# controleo3_clone.net
KiCad netlist of a schematic drawn in Altium Designer
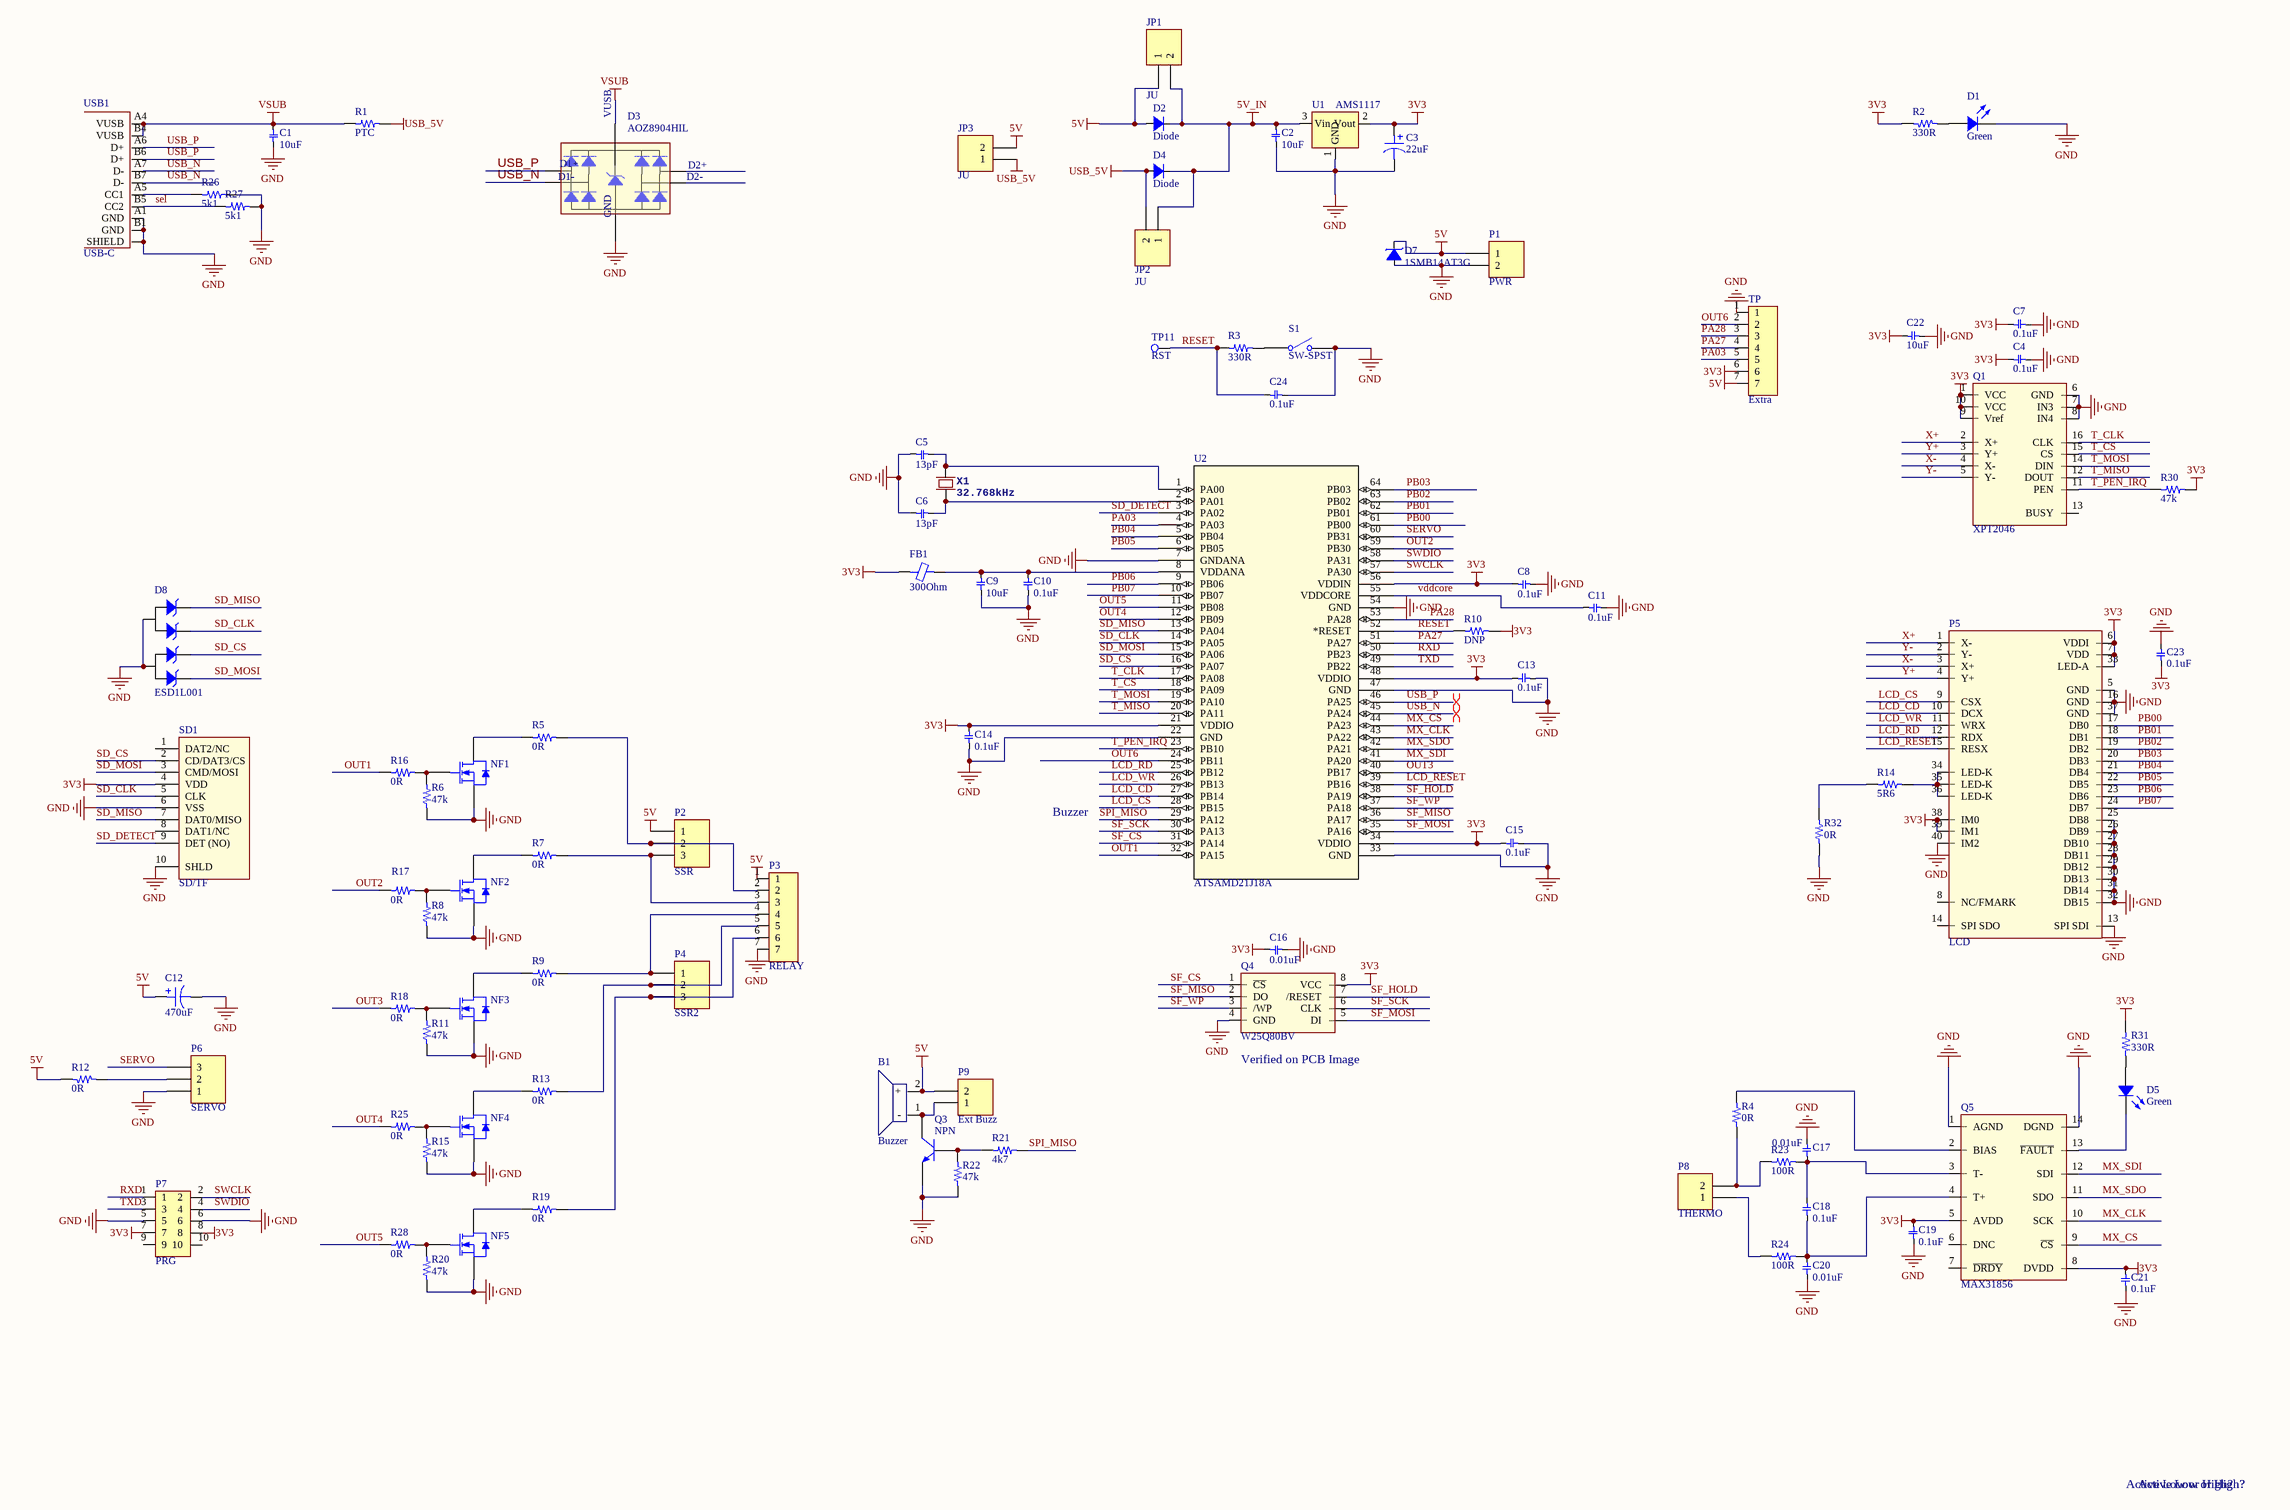
[diagram p0: controleo3_clone.SchDoc]

(export (version "E")
  (design (tool "Eeschema 10.0.6"))
  (components
    (comp (ref "B1") (value "Buzzer") (footprint "Buzzer") (libsource (lib "BMI") (part "Buzzer")))
    (comp (ref "C1")
      (value "10uF")
      (footprint "CAP 0805/2012 RF")
      (description "SMT Capacitor")
      (libsource (lib "Passives") (part "Capacitor Mini Symbol"))
    )
    (comp (ref "C2")
      (value "10uF")
      (footprint "CAP 0805/2012 RF")
      (description "SMT Capacitor")
      (libsource (lib "Passives") (part "Capacitor Mini Symbol"))
    )
    (comp (ref "C3")
      (value "22uF")
      (footprint "CAP Pol 1210/3225 - 2.5MM")
      (libsource (lib "Passives") (part "SMT Tantalum Capacitor"))
    )
    (comp (ref "C4")
      (value "0.1uF")
      (footprint "CAP 0603 RF")
      (description "SMT Capacitor")
      (libsource (lib "Passives") (part "Capacitor Mini Symbol"))
    )
    (comp (ref "C5")
      (value "13pF")
      (footprint "CAP 0603 RF")
      (description "SMT Capacitor")
      (libsource (lib "Passives") (part "Capacitor Mini Symbol"))
    )
    (comp (ref "C6")
      (value "13pF")
      (footprint "CAP 0603 RF")
      (description "SMT Capacitor")
      (libsource (lib "Passives") (part "Capacitor Mini Symbol"))
    )
    (comp (ref "C7")
      (value "0.1uF")
      (footprint "CAP 0603 RF")
      (description "SMT Capacitor")
      (libsource (lib "Passives") (part "Capacitor Mini Symbol"))
    )
    (comp (ref "C8")
      (value "0.1uF")
      (footprint "CAP 0603 RF")
      (description "SMT Capacitor")
      (libsource (lib "Passives") (part "Capacitor Mini Symbol"))
    )
    (comp (ref "C9")
      (value "10uF")
      (footprint "CAP 0603 RF")
      (description "SMT Capacitor")
      (libsource (lib "Passives") (part "Capacitor Mini Symbol"))
    )
    (comp (ref "C10")
      (value "0.1uF")
      (footprint "CAP 0603 RF")
      (description "SMT Capacitor")
      (libsource (lib "Passives") (part "Capacitor Mini Symbol"))
    )
    (comp (ref "C11")
      (value "0.1uF")
      (footprint "CAP 0603 RF")
      (description "SMT Capacitor")
      (libsource (lib "Passives") (part "Capacitor Mini Symbol"))
    )
    (comp (ref "C12")
      (value "470uF")
      (footprint "CAP ALUM 8.0MM Size E")
      (description "SMT Aluminum Capacitor")
      (libsource (lib "Passives") (part "SMT Aluminum Capacitor"))
    )
    (comp (ref "C13")
      (value "0.1uF")
      (footprint "CAP 0603 RF")
      (description "SMT Capacitor")
      (libsource (lib "Passives") (part "Capacitor Mini Symbol"))
    )
    (comp (ref "C14")
      (value "0.1uF")
      (footprint "CAP 0603 RF")
      (description "SMT Capacitor")
      (libsource (lib "Passives") (part "Capacitor Mini Symbol"))
    )
    (comp (ref "C15")
      (value "0.1uF")
      (footprint "CAP 0603 RF")
      (description "SMT Capacitor")
      (libsource (lib "Passives") (part "Capacitor Mini Symbol"))
    )
    (comp (ref "C16")
      (value "0.01uF")
      (footprint "CAP 0603 RF")
      (description "SMT Capacitor")
      (libsource (lib "Passives") (part "Capacitor Mini Symbol"))
    )
    (comp (ref "C17")
      (value "0.01uF")
      (footprint "CAP 0603 RF")
      (description "SMT Capacitor")
      (libsource (lib "Passives") (part "Capacitor Mini Symbol"))
    )
    (comp (ref "C18")
      (value "0.1uF")
      (footprint "CAP 0603 RF")
      (description "SMT Capacitor")
      (libsource (lib "Passives") (part "Capacitor Mini Symbol"))
    )
    (comp (ref "C19")
      (value "0.1uF")
      (footprint "CAP 0603 RF")
      (description "SMT Capacitor")
      (libsource (lib "Passives") (part "Capacitor Mini Symbol"))
    )
    (comp (ref "C20")
      (value "0.01uF")
      (footprint "CAP 0603 RF")
      (description "SMT Capacitor")
      (libsource (lib "Passives") (part "Capacitor Mini Symbol"))
    )
    (comp (ref "C21")
      (value "0.1uF")
      (footprint "CAP 0603 RF")
      (description "SMT Capacitor")
      (libsource (lib "Passives") (part "Capacitor Mini Symbol"))
    )
    (comp (ref "C22")
      (value "10uF")
      (footprint "CAP 0805/2012 RF")
      (description "SMT Capacitor")
      (libsource (lib "Passives") (part "Capacitor Mini Symbol"))
    )
    (comp (ref "C23")
      (value "0.1uF")
      (footprint "CAP 0603 RF")
      (description "SMT Capacitor")
      (libsource (lib "Passives") (part "Capacitor Mini Symbol"))
    )
    (comp (ref "C24")
      (value "0.1uF")
      (footprint "CAP 0603 RF")
      (description "SMT Capacitor")
      (libsource (lib "Passives") (part "Capacitor Mini Symbol"))
    )
    (comp (ref "D1")
      (value "Green")
      (footprint "LED 0603/1608 RF - Red")
      (description "Chip LED")
      (libsource (lib "BMI") (part "LED"))
    )
    (comp (ref "D2") (value "Diode") (footprint "SOD-123F") (libsource (lib "BMI") (part "Diode")))
    (comp (ref "D3")
      (value "AOZ8904HIL")
      (footprint "SOT-23 (6) - Medium")
      (description "ESD Protection Diode")
      (libsource (lib "BMI") (part "ESD Diode USB"))
    )
    (comp (ref "D4") (value "Diode") (footprint "SOD-123F") (libsource (lib "BMI") (part "Diode")))
    (comp (ref "D5")
      (value "Green")
      (footprint "LED 0603/1608 RF - Red")
      (description "Chip LED")
      (libsource (lib "BMI") (part "LED"))
    )
    (comp (ref "D7")
      (value "1SMB14AT3G")
      (footprint "SMB")
      (description "TVS Diode")
      (libsource (lib "BMI") (part "TVS Diode"))
    )
    (comp (ref "D8")
      (value "ESD1L001")
      (footprint "SC-70-6 - NC7WZ16-D")
      (description "ESD Protection Diode Array")
      (libsource (lib "BMI") (part "ESD Diode Array"))
    )
    (comp (ref "FB1")
      (value "300Ohm")
      (footprint "RES 0603/1608 RF")
      (description "SMT Ferrite Chip")
      (libsource (lib "Passives") (part "Ferrite Chip"))
    )
    (comp (ref "JP1")
      (value "JU")
      (footprint "J2")
      (description "Header, 2-Pin, Right Angle")
      (fields (field (name "PUBLISHER") "Altium Limited"))
      (libsource (lib "") (part "Header 2H_1"))
    )
    (comp (ref "JP2")
      (value "JU")
      (footprint "J2")
      (description "Header, 2-Pin, Right Angle")
      (fields (field (name "PUBLISHER") "Altium Limited"))
      (libsource (lib "BMI") (part "Header 2H"))
    )
    (comp (ref "JP3")
      (value "JU")
      (footprint "J2")
      (description "Header, 2-Pin, Right Angle")
      (fields (field (name "PUBLISHER") "Altium Limited"))
      (libsource (lib "") (part "Header 2H_2"))
    )
    (comp (ref "NF1")
      (value "~")
      (footprint "SOT-23")
      (description "N-Channel MOSFET")
      (libsource (lib "BMI") (part "N MOSFET"))
    )
    (comp (ref "NF2")
      (value "~")
      (footprint "SOT-23")
      (description "N-Channel MOSFET")
      (libsource (lib "BMI") (part "N MOSFET"))
    )
    (comp (ref "NF3")
      (value "~")
      (footprint "SOT-23")
      (description "N-Channel MOSFET")
      (libsource (lib "BMI") (part "N MOSFET"))
    )
    (comp (ref "NF4")
      (value "~")
      (footprint "SOT-23")
      (description "N-Channel MOSFET")
      (libsource (lib "BMI") (part "N MOSFET"))
    )
    (comp (ref "NF5")
      (value "~")
      (footprint "SOT-23")
      (description "N-Channel MOSFET")
      (libsource (lib "BMI") (part "N MOSFET"))
    )
    (comp (ref "P1")
      (value "PWR")
      (footprint "W237-102")
      (description "Header, 2-Pin, Right Angle")
      (fields (field (name "PUBLISHER") "Altium Limited"))
      (libsource (lib "") (part "Header 2H_3"))
    )
    (comp (ref "P2")
      (value "SSR")
      (footprint "W237-103")
      (description "Header, 3-Pin, Right Angle")
      (fields (field (name "PUBLISHER") "Altium Limited"))
      (libsource (lib "BMI") (part "Header 3H"))
    )
    (comp (ref "P3")
      (value "RELAY")
      (footprint "Header 7P - Tall")
      (libsource (lib "BMI") (part "Header 7P"))
    )
    (comp (ref "P4")
      (value "SSR2")
      (footprint "W237-103")
      (description "Header, 3-Pin, Right Angle")
      (fields (field (name "PUBLISHER") "Altium Limited"))
      (libsource (lib "BMI") (part "Header 3H"))
    )
    (comp (ref "P5")
      (value "LCD")
      (footprint "FPC 0.5 40Pin - Reverse")
      (libsource (lib "BMI") (part "ILI9488 40Pin FPC"))
    )
    (comp (ref "P6")
      (value "SERVO")
      (footprint "Header 3P - Outline")
      (description "Header, 3-Pin, Right Angle")
      (fields (field (name "PUBLISHER") "Altium Limited"))
      (libsource (lib "") (part "Header 3H_1"))
    )
    (comp (ref "P7") (value "PRG") (footprint "Header 5*2P") (libsource (lib "BMI") (part "Header 10P 2*5P")))
    (comp (ref "P8")
      (value "THERMO")
      (footprint "W237-102")
      (description "Header, 2-Pin, Right Angle")
      (fields (field (name "PUBLISHER") "Altium Limited"))
      (libsource (lib "") (part "Header 2H_2"))
    )
    (comp (ref "P9")
      (value "Ext Buzz")
      (footprint "PH2 2 Pin")
      (description "Header, 2-Pin, Right Angle")
      (fields (field (name "PUBLISHER") "Altium Limited"))
      (libsource (lib "") (part "Header 2H_1"))
    )
    (comp (ref "Q1") (value "XPT2046") (footprint "TSSOP16") (libsource (lib "BMI") (part "XPT2046")))
    (comp (ref "Q3")
      (value "NPN")
      (footprint "SOT-23")
      (description "NPN Transistor")
      (fields (field (name "PUBLISHER") "Altium Limited"))
      (libsource (lib "BMI") (part "NPN"))
    )
    (comp (ref "Q4")
      (value "W25Q80BV")
      (footprint "SOIC8 - 208-mil")
      (libsource (lib "BMI") (part "W25Q80BV"))
    )
    (comp (ref "Q5") (value "MAX31856") (footprint "TSSOP14") (libsource (lib "BMI") (part "MAX31856MUD")))
    (comp (ref "R1")
      (value "PTC")
      (footprint "RES 0805/2012 RF")
      (description "SMT Resistor")
      (libsource (lib "Passives") (part "Resistor"))
    )
    (comp (ref "R2")
      (value "330R")
      (footprint "RES 0603 RF")
      (description "SMT Resistor")
      (libsource (lib "Passives") (part "Resistor"))
    )
    (comp (ref "R3")
      (value "330R")
      (footprint "RES 0603 RF")
      (description "SMT Resistor")
      (libsource (lib "Passives") (part "Resistor"))
    )
    (comp (ref "R4")
      (value "0R")
      (footprint "RES 0603 RF")
      (description "SMT Resistor")
      (libsource (lib "Passives") (part "Resistor"))
    )
    (comp (ref "R5")
      (value "0R")
      (footprint "RES 0805/2012 RF")
      (description "SMT Resistor")
      (libsource (lib "Passives") (part "Resistor"))
    )
    (comp (ref "R6")
      (value "47k")
      (footprint "RES 0603 RF")
      (description "SMT Resistor")
      (libsource (lib "Passives") (part "Resistor"))
    )
    (comp (ref "R7")
      (value "0R")
      (footprint "RES 0805/2012 RF")
      (description "SMT Resistor")
      (libsource (lib "Passives") (part "Resistor"))
    )
    (comp (ref "R8")
      (value "47k")
      (footprint "RES 0603 RF")
      (description "SMT Resistor")
      (libsource (lib "Passives") (part "Resistor"))
    )
    (comp (ref "R9")
      (value "0R")
      (footprint "RES 0805/2012 RF")
      (description "SMT Resistor")
      (libsource (lib "Passives") (part "Resistor"))
    )
    (comp (ref "R10")
      (value "DNP")
      (footprint "RES 0603 RF")
      (description "SMT Resistor")
      (libsource (lib "Passives") (part "Resistor"))
    )
    (comp (ref "R11")
      (value "47k")
      (footprint "RES 0603 RF")
      (description "SMT Resistor")
      (libsource (lib "Passives") (part "Resistor"))
    )
    (comp (ref "R12")
      (value "0R")
      (footprint "RES 0805/2012 RF")
      (description "SMT Resistor")
      (libsource (lib "Passives") (part "Resistor"))
    )
    (comp (ref "R13")
      (value "0R")
      (footprint "RES 0805/2012 RF")
      (description "SMT Resistor")
      (libsource (lib "Passives") (part "Resistor"))
    )
    (comp (ref "R14")
      (value "5R6")
      (footprint "RES 0603 RF")
      (description "SMT Resistor")
      (libsource (lib "Passives") (part "Resistor"))
    )
    (comp (ref "R15")
      (value "47k")
      (footprint "RES 0603 RF")
      (description "SMT Resistor")
      (libsource (lib "Passives") (part "Resistor"))
    )
    (comp (ref "R16")
      (value "0R")
      (footprint "RES 0603 RF")
      (description "SMT Resistor")
      (libsource (lib "Passives") (part "Resistor"))
    )
    (comp (ref "R17")
      (value "0R")
      (footprint "RES 0603 RF")
      (description "SMT Resistor")
      (libsource (lib "Passives") (part "Resistor"))
    )
    (comp (ref "R18")
      (value "0R")
      (footprint "RES 0603 RF")
      (description "SMT Resistor")
      (libsource (lib "Passives") (part "Resistor"))
    )
    (comp (ref "R19")
      (value "0R")
      (footprint "RES 0805/2012 RF")
      (description "SMT Resistor")
      (libsource (lib "Passives") (part "Resistor"))
    )
    (comp (ref "R20")
      (value "47k")
      (footprint "RES 0603 RF")
      (description "SMT Resistor")
      (libsource (lib "Passives") (part "Resistor"))
    )
    (comp (ref "R21")
      (value "4k7")
      (footprint "RES 0603 RF")
      (description "SMT Resistor")
      (libsource (lib "Passives") (part "Resistor"))
    )
    (comp (ref "R22")
      (value "47k")
      (footprint "RES 0603 RF")
      (description "SMT Resistor")
      (libsource (lib "Passives") (part "Resistor"))
    )
    (comp (ref "R23")
      (value "100R")
      (footprint "RES 0603 RF")
      (description "SMT Resistor")
      (libsource (lib "Passives") (part "Resistor"))
    )
    (comp (ref "R24")
      (value "100R")
      (footprint "RES 0603 RF")
      (description "SMT Resistor")
      (libsource (lib "Passives") (part "Resistor"))
    )
    (comp (ref "R25")
      (value "0R")
      (footprint "RES 0603 RF")
      (description "SMT Resistor")
      (libsource (lib "Passives") (part "Resistor"))
    )
    (comp (ref "R26")
      (value "5k1")
      (footprint "RES 0603 RF")
      (description "SMT Resistor")
      (libsource (lib "Passives") (part "Resistor"))
    )
    (comp (ref "R27")
      (value "5k1")
      (footprint "RES 0603 RF")
      (description "SMT Resistor")
      (libsource (lib "Passives") (part "Resistor"))
    )
    (comp (ref "R28")
      (value "0R")
      (footprint "RES 0603 RF")
      (description "SMT Resistor")
      (libsource (lib "Passives") (part "Resistor"))
    )
    (comp (ref "R30")
      (value "47k")
      (footprint "RES 0603 RF")
      (description "SMT Resistor")
      (libsource (lib "Passives") (part "Resistor"))
    )
    (comp (ref "R31")
      (value "330R")
      (footprint "RES 0603 RF")
      (description "SMT Resistor")
      (libsource (lib "Passives") (part "Resistor"))
    )
    (comp (ref "R32")
      (value "0R")
      (footprint "RES 0603 RF")
      (description "SMT Resistor")
      (libsource (lib "Passives") (part "Resistor"))
    )
    (comp (ref "S1")
      (value "SW-SPST")
      (footprint "SMD Button 4x4")
      (description "Single-Pole, Single-Throw Switch")
      (fields (field (name "PUBLISHER") "Altium Limited"))
      (libsource (lib "BMI") (part "SW-SPST"))
    )
    (comp (ref "SD1")
      (value "SD/TF")
      (footprint "SD/TF Card Socket")
      (libsource (lib "BMI") (part "SD-FOXCONN"))
    )
    (comp (ref "TP") (value "Extra") (footprint "Header 7P") (libsource (lib "BMI") (part "Header 7P")))
    (comp (ref "TP11") (value "RST") (footprint "Header 1P") (libsource (lib "Passives") (part "Test Point")))
    (comp (ref "U1")
      (value "AMS1117")
      (footprint "SOT-223 2,4 Jumper")
      (description "Fixed Voltage Regulator")
      (libsource (lib "BMI") (part "AMS1117"))
    )
    (comp (ref "U2")
      (value "ATSAMD21J18A")
      (footprint "TQFP64_10x10MC_MCH-M")
      (description "No Description Available")
      (fields
        (field (name "MANUFACTURER_PART_NUMBER") "ATSAMD21J18A-AU")
        (field (name "COPYRIGHT") "Copyright (C) 2022 Ultra Librarian. All rights reserved.")
      )
      (libsource (lib "BMI") (part "ATSAMD21J18A-AU"))
    )
    (comp (ref "USB1")
      (value "USB-C")
      (footprint "USBC2")
      (description "USB C mid board connector")
      (libsource (lib "BMI") (part "USB-C"))
    )
    (comp (ref "X1")
      (value "32.768kHz")
      (footprint "TXC-SMD-32X15")
      (libsource (lib "BMI") (part "TXC-CRYSTAL32X15"))
    )
  )
  (nets
    (net (code "1") (name "/LCD_CD") (class "Default")
      (node (ref "P5") (pin "10") (pinfunction "DCX_10") (pintype "power_in"))
      (node (ref "U2") (pin "27") (pinfunction "PB14_27") (pintype "bidirectional"))
    )
    (net (code "2") (name "/LCD_CS") (class "Default")
      (node (ref "P5") (pin "9") (pinfunction "CSX_9") (pintype "power_in"))
      (node (ref "U2") (pin "28") (pinfunction "PB15_28") (pintype "bidirectional"))
    )
    (net (code "3") (name "/LCD_RD") (class "Default")
      (node (ref "P5") (pin "12") (pinfunction "RDX_12") (pintype "power_in"))
      (node (ref "U2") (pin "25") (pinfunction "PB12_25") (pintype "bidirectional"))
    )
    (net (code "4") (name "/LCD_RESET") (class "Default")
      (node (ref "P5") (pin "15") (pinfunction "RESX_15") (pintype "power_in"))
      (node (ref "U2") (pin "39") (pinfunction "PB16_39") (pintype "bidirectional"))
    )
    (net (code "5") (name "/LCD_WR") (class "Default")
      (node (ref "P5") (pin "11") (pinfunction "WRX_11") (pintype "power_in"))
      (node (ref "U2") (pin "26") (pinfunction "PB13_26") (pintype "bidirectional"))
    )
    (net (code "6") (name "/MX_CLK") (class "Default")
      (node (ref "Q5") (pin "10") (pinfunction "SCK_10") (pintype "power_in"))
      (node (ref "U2") (pin "43") (pinfunction "PA22_43") (pintype "bidirectional"))
    )
    (net (code "7") (name "/MX_CS") (class "Default")
      (node (ref "Q5") (pin "9") (pinfunction "~{CS}_9") (pintype "power_in"))
      (node (ref "U2") (pin "44") (pinfunction "PA23_44") (pintype "bidirectional"))
    )
    (net (code "8") (name "/MX_SDI") (class "Default")
      (node (ref "Q5") (pin "12") (pinfunction "SDI_12") (pintype "power_in"))
      (node (ref "U2") (pin "41") (pinfunction "PA20_41") (pintype "bidirectional"))
    )
    (net (code "9") (name "/MX_SDO") (class "Default")
      (node (ref "Q5") (pin "11") (pinfunction "SDO_11") (pintype "power_in"))
      (node (ref "U2") (pin "42") (pinfunction "PA21_42") (pintype "bidirectional"))
    )
    (net (code "10") (name "/OUT1") (class "Default")
      (node (ref "R16") (pin "2") (pinfunction "2_2") (pintype "passive"))
      (node (ref "U2") (pin "32") (pinfunction "PA15_32") (pintype "bidirectional"))
    )
    (net (code "11") (name "/OUT2") (class "Default")
      (node (ref "R17") (pin "2") (pinfunction "2_2") (pintype "passive"))
      (node (ref "U2") (pin "59") (pinfunction "PB30_59") (pintype "bidirectional"))
    )
    (net (code "12") (name "/OUT3") (class "Default")
      (node (ref "R18") (pin "2") (pinfunction "2_2") (pintype "passive"))
      (node (ref "U2") (pin "40") (pinfunction "PB17_40") (pintype "bidirectional"))
    )
    (net (code "13") (name "/OUT4") (class "Default")
      (node (ref "R25") (pin "2") (pinfunction "2_2") (pintype "passive"))
      (node (ref "U2") (pin "12") (pinfunction "PB09_12") (pintype "bidirectional"))
    )
    (net (code "14") (name "/OUT5") (class "Default")
      (node (ref "R28") (pin "2") (pinfunction "2_2") (pintype "passive"))
      (node (ref "U2") (pin "11") (pinfunction "PB08_11") (pintype "bidirectional"))
    )
    (net (code "15") (name "/OUT6") (class "Default")
      (node (ref "TP") (pin "2") (pinfunction "2_2") (pintype "passive"))
      (node (ref "U2") (pin "24") (pinfunction "PB11_24") (pintype "bidirectional"))
    )
    (net (code "16") (name "/PA03") (class "Default")
      (node (ref "TP") (pin "5") (pinfunction "5_5") (pintype "passive"))
      (node (ref "U2") (pin "4") (pinfunction "PA03_4") (pintype "bidirectional"))
    )
    (net (code "17") (name "/PA27") (class "Default")
      (node (ref "TP") (pin "4") (pinfunction "4_4") (pintype "passive"))
      (node (ref "U2") (pin "51") (pinfunction "PA27_51") (pintype "bidirectional"))
    )
    (net (code "18") (name "/PA28") (class "Default")
      (node (ref "TP") (pin "3") (pinfunction "3_3") (pintype "passive"))
      (node (ref "U2") (pin "53") (pinfunction "PA28_53") (pintype "bidirectional"))
    )
    (net (code "19") (name "/PB00") (class "Default")
      (node (ref "P5") (pin "17") (pinfunction "DB0_17") (pintype "power_in"))
      (node (ref "U2") (pin "61") (pinfunction "PB00_61") (pintype "bidirectional"))
    )
    (net (code "20") (name "/PB01") (class "Default")
      (node (ref "P5") (pin "18") (pinfunction "DB1_18") (pintype "power_in"))
      (node (ref "U2") (pin "62") (pinfunction "PB01_62") (pintype "bidirectional"))
    )
    (net (code "21") (name "/PB02") (class "Default")
      (node (ref "P5") (pin "19") (pinfunction "DB2_19") (pintype "power_in"))
      (node (ref "U2") (pin "63") (pinfunction "PB02_63") (pintype "bidirectional"))
    )
    (net (code "22") (name "/PB03") (class "Default")
      (node (ref "P5") (pin "20") (pinfunction "DB3_20") (pintype "power_in"))
      (node (ref "U2") (pin "64") (pinfunction "PB03_64") (pintype "bidirectional"))
    )
    (net (code "23") (name "/PB04") (class "Default")
      (node (ref "P5") (pin "21") (pinfunction "DB4_21") (pintype "power_in"))
      (node (ref "U2") (pin "5") (pinfunction "PB04_5") (pintype "bidirectional"))
    )
    (net (code "24") (name "/PB05") (class "Default")
      (node (ref "P5") (pin "22") (pinfunction "DB5_22") (pintype "power_in"))
      (node (ref "U2") (pin "6") (pinfunction "PB05_6") (pintype "bidirectional"))
    )
    (net (code "25") (name "/PB06") (class "Default")
      (node (ref "P5") (pin "23") (pinfunction "DB6_23") (pintype "power_in"))
      (node (ref "U2") (pin "9") (pinfunction "PB06_9") (pintype "bidirectional"))
    )
    (net (code "26") (name "/PB07") (class "Default")
      (node (ref "P5") (pin "24") (pinfunction "DB7_24") (pintype "power_in"))
      (node (ref "U2") (pin "10") (pinfunction "PB07_10") (pintype "bidirectional"))
    )
    (net (code "27") (name "/RESET") (class "Default")
      (node (ref "C24") (pin "2") (pinfunction "2_2") (pintype "passive"))
      (node (ref "R10") (pin "1") (pinfunction "1_1") (pintype "passive"))
      (node (ref "R3") (pin "2") (pinfunction "2_2") (pintype "passive"))
      (node (ref "TP11") (pin "1") (pinfunction "TP_1") (pintype "passive"))
      (node (ref "U2") (pin "52") (pinfunction "*RESET_52") (pintype "passive"))
    )
    (net (code "28") (name "/RXD") (class "Default")
      (node (ref "P7") (pin "1") (pinfunction "1_1") (pintype "passive"))
      (node (ref "U2") (pin "50") (pinfunction "PB23_50") (pintype "bidirectional"))
    )
    (net (code "29") (name "/SD_CLK") (class "Default")
      (node (ref "D8") (pin "2") (pinfunction "2_2") (pintype "passive"))
      (node (ref "SD1") (pin "5") (pinfunction "CLK_5") (pintype "passive"))
      (node (ref "U2") (pin "14") (pinfunction "PA05_14") (pintype "bidirectional"))
    )
    (net (code "30") (name "/SD_CS") (class "Default")
      (node (ref "D8") (pin "4") (pinfunction "4_4") (pintype "passive"))
      (node (ref "SD1") (pin "2") (pinfunction "CD/DAT3/CS_2") (pintype "passive"))
      (node (ref "U2") (pin "16") (pinfunction "PA07_16") (pintype "bidirectional"))
    )
    (net (code "31") (name "/SD_DETECT") (class "Default")
      (node (ref "SD1") (pin "9") (pinfunction "DET_(NO)_9") (pintype "passive"))
      (node (ref "U2") (pin "3") (pinfunction "PA02_3") (pintype "bidirectional"))
    )
    (net (code "32") (name "/SD_MISO") (class "Default")
      (node (ref "D8") (pin "1") (pinfunction "1_1") (pintype "passive"))
      (node (ref "SD1") (pin "7") (pinfunction "DAT0/MISO_7") (pintype "passive"))
      (node (ref "U2") (pin "13") (pinfunction "PA04_13") (pintype "bidirectional"))
    )
    (net (code "33") (name "/SD_MOSI") (class "Default")
      (node (ref "D8") (pin "5") (pinfunction "5_5") (pintype "passive"))
      (node (ref "SD1") (pin "3") (pinfunction "CMD/MOSI_3") (pintype "passive"))
      (node (ref "U2") (pin "15") (pinfunction "PA06_15") (pintype "bidirectional"))
    )
    (net (code "34") (name "/SERVO") (class "Default")
      (node (ref "P6") (pin "3") (pinfunction "3_3") (pintype "passive"))
      (node (ref "U2") (pin "60") (pinfunction "PB31_60") (pintype "bidirectional"))
    )
    (net (code "35") (name "/SF_CS") (class "Default")
      (node (ref "Q4") (pin "1") (pinfunction "~{CS}_1") (pintype "power_in"))
      (node (ref "U2") (pin "31") (pinfunction "PA14_31") (pintype "bidirectional"))
    )
    (net (code "36") (name "/SF_HOLD") (class "Default")
      (node (ref "Q4") (pin "7") (pinfunction "/RESET_7") (pintype "power_in"))
      (node (ref "U2") (pin "38") (pinfunction "PA19_38") (pintype "bidirectional"))
    )
    (net (code "37") (name "/SF_MISO") (class "Default")
      (node (ref "Q4") (pin "2") (pinfunction "DO_2") (pintype "power_in"))
      (node (ref "U2") (pin "36") (pinfunction "PA17_36") (pintype "bidirectional"))
    )
    (net (code "38") (name "/SF_MOSI") (class "Default")
      (node (ref "Q4") (pin "5") (pinfunction "DI_5") (pintype "power_in"))
      (node (ref "U2") (pin "35") (pinfunction "PA16_35") (pintype "bidirectional"))
    )
    (net (code "39") (name "/SF_SCK") (class "Default")
      (node (ref "Q4") (pin "6") (pinfunction "CLK_6") (pintype "power_in"))
      (node (ref "U2") (pin "30") (pinfunction "PA13_30") (pintype "bidirectional"))
    )
    (net (code "40") (name "/SF_WP") (class "Default")
      (node (ref "Q4") (pin "3") (pinfunction "/WP_3") (pintype "power_in"))
      (node (ref "U2") (pin "37") (pinfunction "PA18_37") (pintype "bidirectional"))
    )
    (net (code "41") (name "/SPI_MISO") (class "Default")
      (node (ref "R21") (pin "2") (pinfunction "2_2") (pintype "passive"))
      (node (ref "U2") (pin "29") (pinfunction "PA12_29") (pintype "bidirectional"))
    )
    (net (code "42") (name "/SWCLK") (class "Default")
      (node (ref "P7") (pin "2") (pinfunction "2_2") (pintype "passive"))
      (node (ref "U2") (pin "57") (pinfunction "PA30_57") (pintype "bidirectional"))
    )
    (net (code "43") (name "/SWDIO") (class "Default")
      (node (ref "P7") (pin "4") (pinfunction "4_4") (pintype "passive"))
      (node (ref "U2") (pin "58") (pinfunction "PA31_58") (pintype "bidirectional"))
    )
    (net (code "44") (name "/TXD") (class "Default")
      (node (ref "P7") (pin "3") (pinfunction "3_3") (pintype "passive"))
      (node (ref "U2") (pin "49") (pinfunction "PB22_49") (pintype "bidirectional"))
    )
    (net (code "45") (name "/T_CLK") (class "Default")
      (node (ref "Q1") (pin "16") (pinfunction "CLK_16") (pintype "power_in"))
      (node (ref "U2") (pin "17") (pinfunction "PA08_17") (pintype "bidirectional"))
    )
    (net (code "46") (name "/T_CS") (class "Default")
      (node (ref "Q1") (pin "15") (pinfunction "CS_15") (pintype "power_in"))
      (node (ref "U2") (pin "18") (pinfunction "PA09_18") (pintype "bidirectional"))
    )
    (net (code "47") (name "/T_MISO") (class "Default")
      (node (ref "Q1") (pin "12") (pinfunction "DOUT_12") (pintype "power_in"))
      (node (ref "U2") (pin "20") (pinfunction "PA11_20") (pintype "bidirectional"))
    )
    (net (code "48") (name "/T_MOSI") (class "Default")
      (node (ref "Q1") (pin "14") (pinfunction "DIN_14") (pintype "power_in"))
      (node (ref "U2") (pin "19") (pinfunction "PA10_19") (pintype "bidirectional"))
    )
    (net (code "49") (name "/T_PEN_IRQ") (class "Default")
      (node (ref "Q1") (pin "11") (pinfunction "PEN_11") (pintype "power_in"))
      (node (ref "R30") (pin "2") (pinfunction "2_2") (pintype "passive"))
      (node (ref "U2") (pin "23") (pinfunction "PB10_23") (pintype "bidirectional"))
    )
    (net (code "50") (name "/USB_N") (class "Default")
      (node (ref "D3") (pin "6") (pinfunction "D1-_6") (pintype "passive"))
      (node (ref "U2") (pin "45") (pinfunction "PA24_45") (pintype "bidirectional"))
      (node (ref "USB1") (pin "A7") (pinfunction "D-_A7") (pintype "passive"))
      (node (ref "USB1") (pin "B7") (pinfunction "D-_B7") (pintype "passive"))
    )
    (net (code "51") (name "/USB_P") (class "Default")
      (node (ref "D3") (pin "1") (pinfunction "D1+_1") (pintype "passive"))
      (node (ref "U2") (pin "46") (pinfunction "PA25_46") (pintype "bidirectional"))
      (node (ref "USB1") (pin "A6") (pinfunction "D+_A6") (pintype "passive"))
      (node (ref "USB1") (pin "B6") (pinfunction "D+_B6") (pintype "passive"))
    )
    (net (code "52") (name "/X+") (class "Default")
      (node (ref "P5") (pin "1") (pinfunction "X-_1") (pintype "power_in"))
      (node (ref "Q1") (pin "2") (pinfunction "X+_2") (pintype "power_in"))
    )
    (net (code "53") (name "/X-") (class "Default")
      (node (ref "P5") (pin "3") (pinfunction "X+_3") (pintype "power_in"))
      (node (ref "Q1") (pin "4") (pinfunction "X-_4") (pintype "power_in"))
    )
    (net (code "54") (name "/Y+") (class "Default")
      (node (ref "P5") (pin "4") (pinfunction "Y+_4") (pintype "power_in"))
      (node (ref "Q1") (pin "3") (pinfunction "Y+_3") (pintype "power_in"))
    )
    (net (code "55") (name "/Y-") (class "Default")
      (node (ref "P5") (pin "2") (pinfunction "Y-_2") (pintype "power_in"))
      (node (ref "Q1") (pin "5") (pinfunction "Y-_5") (pintype "power_in"))
    )
    (net (code "56") (name "/sel") (class "Default")
      (node (ref "R27") (pin "1") (pinfunction "1_1") (pintype "passive"))
      (node (ref "USB1") (pin "B5") (pinfunction "CC2_B5") (pintype "passive"))
    )
    (net (code "57") (name "/vddcore") (class "Default")
      (node (ref "C11") (pin "1") (pinfunction "1_1") (pintype "passive"))
      (node (ref "U2") (pin "55") (pinfunction "VDDCORE_55") (pintype "power_in"))
    )
    (net (code "58") (name "3V3") (class "Default")
      (node (ref "C13") (pin "2") (pinfunction "2_2") (pintype "passive"))
      (node (ref "C14") (pin "2") (pinfunction "2_2") (pintype "passive"))
      (node (ref "C15") (pin "2") (pinfunction "2_2") (pintype "passive"))
      (node (ref "C16") (pin "1") (pinfunction "1_1") (pintype "passive"))
      (node (ref "C19") (pin "2") (pinfunction "2_2") (pintype "passive"))
      (node (ref "C21") (pin "2") (pinfunction "2_2") (pintype "passive"))
      (node (ref "C22") (pin "2") (pinfunction "2_2") (pintype "passive"))
      (node (ref "C23") (pin "2") (pinfunction "2_2") (pintype "passive"))
      (node (ref "C3") (pin "1") (pinfunction "1_1") (pintype "passive"))
      (node (ref "C4") (pin "2") (pinfunction "2_2") (pintype "passive"))
      (node (ref "C7") (pin "2") (pinfunction "2_2") (pintype "passive"))
      (node (ref "C8") (pin "1") (pinfunction "1_1") (pintype "passive"))
      (node (ref "FB1") (pin "1") (pinfunction "1_1") (pintype "passive"))
      (node (ref "P5") (pin "33") (pinfunction "LED-A_33") (pintype "power_in"))
      (node (ref "P5") (pin "38") (pinfunction "IM0_38") (pintype "power_in"))
      (node (ref "P5") (pin "39") (pinfunction "IM1_39") (pintype "power_in"))
      (node (ref "P5") (pin "6") (pinfunction "VDDI_6") (pintype "power_in"))
      (node (ref "P5") (pin "7") (pinfunction "VDD_7") (pintype "power_in"))
      (node (ref "P7") (pin "7") (pinfunction "7_7") (pintype "passive"))
      (node (ref "P7") (pin "8") (pinfunction "8_8") (pintype "passive"))
      (node (ref "Q1") (pin "1") (pinfunction "VCC_1") (pintype "power_in"))
      (node (ref "Q1") (pin "10") (pinfunction "VCC_10") (pintype "power_in"))
      (node (ref "Q1") (pin "9") (pinfunction "Vref_9") (pintype "power_in"))
      (node (ref "Q4") (pin "8") (pinfunction "VCC_8") (pintype "power_in"))
      (node (ref "Q5") (pin "5") (pinfunction "AVDD_5") (pintype "power_in"))
      (node (ref "Q5") (pin "8") (pinfunction "DVDD_8") (pintype "power_in"))
      (node (ref "R10") (pin "2") (pinfunction "2_2") (pintype "passive"))
      (node (ref "R2") (pin "1") (pinfunction "1_1") (pintype "passive"))
      (node (ref "R30") (pin "1") (pinfunction "1_1") (pintype "passive"))
      (node (ref "R31") (pin "1") (pinfunction "1_1") (pintype "passive"))
      (node (ref "SD1") (pin "4") (pinfunction "VDD_4") (pintype "passive"))
      (node (ref "TP") (pin "6") (pinfunction "6_6") (pintype "passive"))
      (node (ref "U1") (pin "2") (pinfunction "Vout_2") (pintype "passive"))
      (node (ref "U2") (pin "21") (pinfunction "VDDIO_21") (pintype "power_in"))
      (node (ref "U2") (pin "34") (pinfunction "VDDIO_34") (pintype "power_in"))
      (node (ref "U2") (pin "48") (pinfunction "VDDIO_48") (pintype "power_in"))
      (node (ref "U2") (pin "56") (pinfunction "VDDIN_56") (pintype "power_in"))
    )
    (net (code "59") (name "5V") (class "Default")
      (node (ref "B1") (pin "2") (pinfunction "+_2") (pintype "passive"))
      (node (ref "C12") (pin "1") (pinfunction "1_1") (pintype "passive"))
      (node (ref "D2") (pin "1") (pinfunction "1_1") (pintype "passive"))
      (node (ref "D7") (pin "2") (pinfunction "2_2") (pintype "passive"))
      (node (ref "JP1") (pin "1") (pinfunction "1_1") (pintype "passive"))
      (node (ref "JP3") (pin "2") (pinfunction "2_2") (pintype "passive"))
      (node (ref "P1") (pin "1") (pinfunction "1_1") (pintype "passive"))
      (node (ref "P2") (pin "1") (pinfunction "1_1") (pintype "passive"))
      (node (ref "P3") (pin "1") (pinfunction "1_1") (pintype "passive"))
      (node (ref "P9") (pin "2") (pinfunction "2_2") (pintype "passive"))
      (node (ref "R12") (pin "1") (pinfunction "1_1") (pintype "passive"))
      (node (ref "TP") (pin "7") (pinfunction "7_7") (pintype "passive"))
    )
    (net (code "60") (name "5V_IN") (class "Default")
      (node (ref "C2") (pin "2") (pinfunction "2_2") (pintype "passive"))
      (node (ref "D2") (pin "2") (pinfunction "2_2") (pintype "passive"))
      (node (ref "D4") (pin "2") (pinfunction "2_2") (pintype "passive"))
      (node (ref "JP1") (pin "2") (pinfunction "2_2") (pintype "passive"))
      (node (ref "JP2") (pin "1") (pinfunction "1_1") (pintype "passive"))
      (node (ref "U1") (pin "3") (pinfunction "Vin_3") (pintype "power_in"))
    )
    (net (code "61") (name "GND") (class "Default")
      (node (ref "C1") (pin "2") (pinfunction "2_2") (pintype "passive"))
      (node (ref "C10") (pin "1") (pinfunction "1_1") (pintype "passive"))
      (node (ref "C11") (pin "2") (pinfunction "2_2") (pintype "passive"))
      (node (ref "C12") (pin "2") (pinfunction "2_2") (pintype "passive"))
      (node (ref "C13") (pin "1") (pinfunction "1_1") (pintype "passive"))
      (node (ref "C14") (pin "1") (pinfunction "1_1") (pintype "passive"))
      (node (ref "C15") (pin "1") (pinfunction "1_1") (pintype "passive"))
      (node (ref "C16") (pin "2") (pinfunction "2_2") (pintype "passive"))
      (node (ref "C17") (pin "2") (pinfunction "2_2") (pintype "passive"))
      (node (ref "C19") (pin "1") (pinfunction "1_1") (pintype "passive"))
      (node (ref "C2") (pin "1") (pinfunction "1_1") (pintype "passive"))
      (node (ref "C20") (pin "1") (pinfunction "1_1") (pintype "passive"))
      (node (ref "C21") (pin "1") (pinfunction "1_1") (pintype "passive"))
      (node (ref "C22") (pin "1") (pinfunction "1_1") (pintype "passive"))
      (node (ref "C23") (pin "1") (pinfunction "1_1") (pintype "passive"))
      (node (ref "C24") (pin "1") (pinfunction "1_1") (pintype "passive"))
      (node (ref "C3") (pin "2") (pinfunction "2_2") (pintype "passive"))
      (node (ref "C4") (pin "1") (pinfunction "1_1") (pintype "passive"))
      (node (ref "C5") (pin "2") (pinfunction "2_2") (pintype "passive"))
      (node (ref "C6") (pin "2") (pinfunction "2_2") (pintype "passive"))
      (node (ref "C7") (pin "1") (pinfunction "1_1") (pintype "passive"))
      (node (ref "C8") (pin "2") (pinfunction "2_2") (pintype "passive"))
      (node (ref "C9") (pin "1") (pinfunction "1_1") (pintype "passive"))
      (node (ref "D1") (pin "2") (pinfunction "2_2") (pintype "passive"))
      (node (ref "D3") (pin "2") (pinfunction "GND_2") (pintype "passive"))
      (node (ref "D7") (pin "1") (pinfunction "1_1") (pintype "passive"))
      (node (ref "D8") (pin "3") (pinfunction "3_3") (pintype "passive"))
      (node (ref "D8") (pin "6") (pinfunction "6_6") (pintype "passive"))
      (node (ref "NF1") (pin "3") (pinfunction "S_3") (pintype "passive"))
      (node (ref "NF2") (pin "3") (pinfunction "S_3") (pintype "passive"))
      (node (ref "NF3") (pin "3") (pinfunction "S_3") (pintype "passive"))
      (node (ref "NF4") (pin "3") (pinfunction "S_3") (pintype "passive"))
      (node (ref "NF5") (pin "3") (pinfunction "S_3") (pintype "passive"))
      (node (ref "P1") (pin "2") (pinfunction "2_2") (pintype "passive"))
      (node (ref "P3") (pin "7") (pinfunction "7_7") (pintype "passive"))
      (node (ref "P5") (pin "13") (pinfunction "SPI_SDI_13") (pintype "power_in"))
      (node (ref "P5") (pin "16") (pinfunction "GND_16") (pintype "power_in"))
      (node (ref "P5") (pin "25") (pinfunction "DB8_25") (pintype "power_in"))
      (node (ref "P5") (pin "26") (pinfunction "DB9_26") (pintype "power_in"))
      (node (ref "P5") (pin "27") (pinfunction "DB10_27") (pintype "power_in"))
      (node (ref "P5") (pin "28") (pinfunction "DB11_28") (pintype "power_in"))
      (node (ref "P5") (pin "29") (pinfunction "DB12_29") (pintype "power_in"))
      (node (ref "P5") (pin "30") (pinfunction "DB13_30") (pintype "power_in"))
      (node (ref "P5") (pin "31") (pinfunction "DB14_31") (pintype "power_in"))
      (node (ref "P5") (pin "32") (pinfunction "DB15_32") (pintype "power_in"))
      (node (ref "P5") (pin "37") (pinfunction "GND_37") (pintype "power_in"))
      (node (ref "P5") (pin "40") (pinfunction "IM2_40") (pintype "power_in"))
      (node (ref "P5") (pin "5") (pinfunction "GND_5") (pintype "power_in"))
      (node (ref "P6") (pin "1") (pinfunction "1_1") (pintype "passive"))
      (node (ref "P7") (pin "5") (pinfunction "5_5") (pintype "passive"))
      (node (ref "P7") (pin "6") (pinfunction "6_6") (pintype "passive"))
      (node (ref "Q1") (pin "6") (pinfunction "GND_6") (pintype "power_in"))
      (node (ref "Q1") (pin "7") (pinfunction "IN3_7") (pintype "power_in"))
      (node (ref "Q1") (pin "8") (pinfunction "IN4_8") (pintype "power_in"))
      (node (ref "Q3") (pin "1") (pinfunction "E_1") (pintype "passive"))
      (node (ref "Q4") (pin "4") (pinfunction "GND_4") (pintype "power_in"))
      (node (ref "Q5") (pin "1") (pinfunction "AGND_1") (pintype "power_in"))
      (node (ref "Q5") (pin "14") (pinfunction "DGND_14") (pintype "power_in"))
      (node (ref "R11") (pin "1") (pinfunction "1_1") (pintype "passive"))
      (node (ref "R15") (pin "1") (pinfunction "1_1") (pintype "passive"))
      (node (ref "R20") (pin "1") (pinfunction "1_1") (pintype "passive"))
      (node (ref "R22") (pin "1") (pinfunction "1_1") (pintype "passive"))
      (node (ref "R26") (pin "2") (pinfunction "2_2") (pintype "passive"))
      (node (ref "R27") (pin "2") (pinfunction "2_2") (pintype "passive"))
      (node (ref "R32") (pin "2") (pinfunction "2_2") (pintype "passive"))
      (node (ref "R6") (pin "1") (pinfunction "1_1") (pintype "passive"))
      (node (ref "R8") (pin "1") (pinfunction "1_1") (pintype "passive"))
      (node (ref "S1") (pin "2") (pinfunction "NO_2") (pintype "passive"))
      (node (ref "SD1") (pin "10") (pinfunction "SHLD_10") (pintype "passive"))
      (node (ref "SD1") (pin "6") (pinfunction "VSS_6") (pintype "passive"))
      (node (ref "TP") (pin "1") (pinfunction "1_1") (pintype "passive"))
      (node (ref "U1") (pin "1") (pinfunction "GND_1") (pintype "passive"))
      (node (ref "U2") (pin "22") (pinfunction "GND_22") (pintype "passive"))
      (node (ref "U2") (pin "33") (pinfunction "GND_33") (pintype "passive"))
      (node (ref "U2") (pin "47") (pinfunction "GND_47") (pintype "passive"))
      (node (ref "U2") (pin "54") (pinfunction "GND_54") (pintype "passive"))
      (node (ref "U2") (pin "7") (pinfunction "GNDANA_7") (pintype "passive"))
      (node (ref "USB1") (pin "1") (pinfunction "SHIELD_1") (pintype "power_in"))
      (node (ref "USB1") (pin "A1") (pinfunction "GND_A1") (pintype "power_in"))
      (node (ref "USB1") (pin "B1") (pinfunction "GND_B1") (pintype "power_in"))
    )
    (net (code "62") (name "Net-(B1--)") (class "Default")
      (node (ref "B1") (pin "1") (pinfunction "-_1") (pintype "passive"))
      (node (ref "P9") (pin "1") (pinfunction "1_1") (pintype "passive"))
      (node (ref "Q3") (pin "3") (pinfunction "C_3") (pintype "passive"))
    )
    (net (code "63") (name "Net-(D1-Pad1)") (class "Default")
      (node (ref "D1") (pin "1") (pinfunction "1_1") (pintype "passive"))
      (node (ref "R2") (pin "2") (pinfunction "2_2") (pintype "passive"))
    )
    (net (code "64") (name "Net-(D5-Pad1)") (class "Default")
      (node (ref "D5") (pin "1") (pinfunction "1_1") (pintype "passive"))
      (node (ref "R31") (pin "2") (pinfunction "2_2") (pintype "passive"))
    )
    (net (code "65") (name "Net-(NF1-D)") (class "Default")
      (node (ref "NF1") (pin "4") (pinfunction "D_4") (pintype "passive"))
      (node (ref "R5") (pin "1") (pinfunction "1_1") (pintype "passive"))
    )
    (net (code "66") (name "Net-(NF1-G)") (class "Default")
      (node (ref "NF1") (pin "1") (pinfunction "G_1") (pintype "passive"))
      (node (ref "R16") (pin "1") (pinfunction "1_1") (pintype "passive"))
      (node (ref "R6") (pin "2") (pinfunction "2_2") (pintype "passive"))
    )
    (net (code "67") (name "Net-(NF2-D)") (class "Default")
      (node (ref "NF2") (pin "4") (pinfunction "D_4") (pintype "passive"))
      (node (ref "R7") (pin "1") (pinfunction "1_1") (pintype "passive"))
    )
    (net (code "68") (name "Net-(NF2-G)") (class "Default")
      (node (ref "NF2") (pin "1") (pinfunction "G_1") (pintype "passive"))
      (node (ref "R17") (pin "1") (pinfunction "1_1") (pintype "passive"))
      (node (ref "R8") (pin "2") (pinfunction "2_2") (pintype "passive"))
    )
    (net (code "69") (name "Net-(NF3-D)") (class "Default")
      (node (ref "NF3") (pin "4") (pinfunction "D_4") (pintype "passive"))
      (node (ref "R9") (pin "1") (pinfunction "1_1") (pintype "passive"))
    )
    (net (code "70") (name "Net-(NF3-G)") (class "Default")
      (node (ref "NF3") (pin "1") (pinfunction "G_1") (pintype "passive"))
      (node (ref "R11") (pin "2") (pinfunction "2_2") (pintype "passive"))
      (node (ref "R18") (pin "1") (pinfunction "1_1") (pintype "passive"))
    )
    (net (code "71") (name "Net-(NF4-D)") (class "Default")
      (node (ref "NF4") (pin "4") (pinfunction "D_4") (pintype "passive"))
      (node (ref "R13") (pin "1") (pinfunction "1_1") (pintype "passive"))
    )
    (net (code "72") (name "Net-(NF4-G)") (class "Default")
      (node (ref "NF4") (pin "1") (pinfunction "G_1") (pintype "passive"))
      (node (ref "R15") (pin "2") (pinfunction "2_2") (pintype "passive"))
      (node (ref "R25") (pin "1") (pinfunction "1_1") (pintype "passive"))
    )
    (net (code "73") (name "Net-(NF5-D)") (class "Default")
      (node (ref "NF5") (pin "4") (pinfunction "D_4") (pintype "passive"))
      (node (ref "R19") (pin "1") (pinfunction "1_1") (pintype "passive"))
    )
    (net (code "74") (name "Net-(NF5-G)") (class "Default")
      (node (ref "NF5") (pin "1") (pinfunction "G_1") (pintype "passive"))
      (node (ref "R20") (pin "2") (pinfunction "2_2") (pintype "passive"))
      (node (ref "R28") (pin "1") (pinfunction "1_1") (pintype "passive"))
    )
    (net (code "75") (name "Net-(P2-Pad2)") (class "Default")
      (node (ref "P2") (pin "2") (pinfunction "2_2") (pintype "passive"))
      (node (ref "P3") (pin "2") (pinfunction "2_2") (pintype "passive"))
      (node (ref "R5") (pin "2") (pinfunction "2_2") (pintype "passive"))
    )
    (net (code "76") (name "Net-(P2-Pad3)") (class "Default")
      (node (ref "P2") (pin "3") (pinfunction "3_3") (pintype "passive"))
      (node (ref "P3") (pin "3") (pinfunction "3_3") (pintype "passive"))
      (node (ref "R7") (pin "2") (pinfunction "2_2") (pintype "passive"))
    )
    (net (code "77") (name "Net-(P3-Pad4)") (class "Default")
      (node (ref "P3") (pin "4") (pinfunction "4_4") (pintype "passive"))
      (node (ref "P4") (pin "1") (pinfunction "1_1") (pintype "passive"))
      (node (ref "R9") (pin "2") (pinfunction "2_2") (pintype "passive"))
    )
    (net (code "78") (name "Net-(P3-Pad5)") (class "Default")
      (node (ref "P3") (pin "5") (pinfunction "5_5") (pintype "passive"))
      (node (ref "P4") (pin "2") (pinfunction "2_2") (pintype "passive"))
      (node (ref "R13") (pin "2") (pinfunction "2_2") (pintype "passive"))
    )
    (net (code "79") (name "Net-(P3-Pad6)") (class "Default")
      (node (ref "P3") (pin "6") (pinfunction "6_6") (pintype "passive"))
      (node (ref "P4") (pin "3") (pinfunction "3_3") (pintype "passive"))
      (node (ref "R19") (pin "2") (pinfunction "2_2") (pintype "passive"))
    )
    (net (code "80") (name "Net-(P5-LED-K-Pad34)") (class "Default")
      (node (ref "P5") (pin "34") (pinfunction "LED-K_34") (pintype "power_in"))
      (node (ref "P5") (pin "35") (pinfunction "LED-K_35") (pintype "power_in"))
      (node (ref "P5") (pin "36") (pinfunction "LED-K_36") (pintype "power_in"))
      (node (ref "R14") (pin "1") (pinfunction "1_1") (pintype "passive"))
    )
    (net (code "81") (name "Net-(P6-Pad2)") (class "Default")
      (node (ref "P6") (pin "2") (pinfunction "2_2") (pintype "passive"))
      (node (ref "R12") (pin "2") (pinfunction "2_2") (pintype "passive"))
    )
    (net (code "82") (name "Net-(P8-Pad1)") (class "Default")
      (node (ref "P8") (pin "1") (pinfunction "1_1") (pintype "passive"))
      (node (ref "R24") (pin "1") (pinfunction "1_1") (pintype "passive"))
    )
    (net (code "83") (name "Net-(P8-Pad2)") (class "Default")
      (node (ref "P8") (pin "2") (pinfunction "2_2") (pintype "passive"))
      (node (ref "R23") (pin "1") (pinfunction "1_1") (pintype "passive"))
      (node (ref "R4") (pin "1") (pinfunction "1_1") (pintype "passive"))
    )
    (net (code "84") (name "Net-(Q3-B)") (class "Default")
      (node (ref "Q3") (pin "2") (pinfunction "B_2") (pintype "passive"))
      (node (ref "R21") (pin "1") (pinfunction "1_1") (pintype "passive"))
      (node (ref "R22") (pin "2") (pinfunction "2_2") (pintype "passive"))
    )
    (net (code "85") (name "Net-(Q5-BIAS)") (class "Default")
      (node (ref "Q5") (pin "2") (pinfunction "BIAS_2") (pintype "power_in"))
      (node (ref "R4") (pin "2") (pinfunction "2_2") (pintype "passive"))
    )
    (net (code "86") (name "Net-(Q5-T+)") (class "Default")
      (node (ref "C18") (pin "1") (pinfunction "1_1") (pintype "passive"))
      (node (ref "C20") (pin "2") (pinfunction "2_2") (pintype "passive"))
      (node (ref "Q5") (pin "4") (pinfunction "T+_4") (pintype "power_in"))
      (node (ref "R24") (pin "2") (pinfunction "2_2") (pintype "passive"))
    )
    (net (code "87") (name "Net-(Q5-T-)") (class "Default")
      (node (ref "C17") (pin "1") (pinfunction "1_1") (pintype "passive"))
      (node (ref "C18") (pin "2") (pinfunction "2_2") (pintype "passive"))
      (node (ref "Q5") (pin "3") (pinfunction "T-_3") (pintype "power_in"))
      (node (ref "R23") (pin "2") (pinfunction "2_2") (pintype "passive"))
    )
    (net (code "88") (name "Net-(Q5-~{FAULT})") (class "Default")
      (node (ref "D5") (pin "2") (pinfunction "2_2") (pintype "passive"))
      (node (ref "Q5") (pin "13") (pinfunction "~{FAULT}_13") (pintype "power_in"))
    )
    (net (code "89") (name "Net-(R14-Pad2)") (class "Default")
      (node (ref "R14") (pin "2") (pinfunction "2_2") (pintype "passive"))
      (node (ref "R32") (pin "1") (pinfunction "1_1") (pintype "passive"))
    )
    (net (code "90") (name "Net-(S1-COMMON)") (class "Default")
      (node (ref "R3") (pin "1") (pinfunction "1_1") (pintype "passive"))
      (node (ref "S1") (pin "1") (pinfunction "COMMON_1") (pintype "passive"))
    )
    (net (code "91") (name "Net-(U2-PA00)") (class "Default")
      (node (ref "C5") (pin "1") (pinfunction "1_1") (pintype "passive"))
      (node (ref "U2") (pin "1") (pinfunction "PA00_1") (pintype "bidirectional"))
      (node (ref "X1") (pin "P$2") (pinfunction "P$2_P$2") (pintype "passive"))
    )
    (net (code "92") (name "Net-(U2-PA01)") (class "Default")
      (node (ref "C6") (pin "1") (pinfunction "1_1") (pintype "passive"))
      (node (ref "U2") (pin "2") (pinfunction "PA01_2") (pintype "bidirectional"))
      (node (ref "X1") (pin "P$1") (pinfunction "P$1_P$1") (pintype "passive"))
    )
    (net (code "93") (name "Net-(U2-VDDANA)") (class "Default")
      (node (ref "C10") (pin "2") (pinfunction "2_2") (pintype "passive"))
      (node (ref "C9") (pin "2") (pinfunction "2_2") (pintype "passive"))
      (node (ref "FB1") (pin "2") (pinfunction "2_2") (pintype "passive"))
      (node (ref "U2") (pin "8") (pinfunction "VDDANA_8") (pintype "power_in"))
    )
    (net (code "94") (name "Net-(USB1-CC1)") (class "Default")
      (node (ref "R26") (pin "1") (pinfunction "1_1") (pintype "passive"))
      (node (ref "USB1") (pin "A5") (pinfunction "CC1_A5") (pintype "passive"))
    )
    (net (code "95") (name "USB_5V") (class "Default")
      (node (ref "D4") (pin "1") (pinfunction "1_1") (pintype "passive"))
      (node (ref "JP2") (pin "2") (pinfunction "2_2") (pintype "passive"))
      (node (ref "JP3") (pin "1") (pinfunction "1_1") (pintype "passive"))
      (node (ref "R1") (pin "2") (pinfunction "2_2") (pintype "passive"))
    )
    (net (code "96") (name "VSUB") (class "Default")
      (node (ref "C1") (pin "1") (pinfunction "1_1") (pintype "passive"))
      (node (ref "D3") (pin "5") (pinfunction "VUSB_5") (pintype "passive"))
      (node (ref "R1") (pin "1") (pinfunction "1_1") (pintype "passive"))
      (node (ref "USB1") (pin "A4") (pinfunction "VUSB_A4") (pintype "power_in"))
      (node (ref "USB1") (pin "B4") (pinfunction "VUSB_B4") (pintype "power_in"))
    )
    (net (code "97") (name "unconnected-(D3-D2+-Pad4)") (class "Default")
      (node (ref "D3") (pin "4") (pinfunction "D2+_4") (pintype "passive"))
    )
    (net (code "98") (name "unconnected-(D3-D2--Pad3)") (class "Default")
      (node (ref "D3") (pin "3") (pinfunction "D2-_3") (pintype "passive"))
    )
    (net (code "99") (name "unconnected-(P5-NC{slash}FMARK-Pad8)") (class "Default")
      (node (ref "P5") (pin "8") (pinfunction "NC/FMARK_8") (pintype "power_in"))
    )
    (net (code "100") (name "unconnected-(P5-SPI_SDO-Pad14)") (class "Default")
      (node (ref "P5") (pin "14") (pinfunction "SPI_SDO_14") (pintype "power_in"))
    )
    (net (code "101") (name "unconnected-(P7-Pad9)") (class "Default")
      (node (ref "P7") (pin "9") (pinfunction "9_9") (pintype "passive"))
    )
    (net (code "102") (name "unconnected-(P7-Pad10)") (class "Default")
      (node (ref "P7") (pin "10") (pinfunction "10_10") (pintype "passive"))
    )
    (net (code "103") (name "unconnected-(Q1-BUSY-Pad13)") (class "Default")
      (node (ref "Q1") (pin "13") (pinfunction "BUSY_13") (pintype "power_in"))
    )
    (net (code "104") (name "unconnected-(Q5-DNC-Pad6)") (class "Default")
      (node (ref "Q5") (pin "6") (pinfunction "DNC_6") (pintype "power_in"))
    )
    (net (code "105") (name "unconnected-(Q5-~{DRDY}-Pad7)") (class "Default")
      (node (ref "Q5") (pin "7") (pinfunction "~{DRDY}_7") (pintype "power_in"))
    )
    (net (code "106") (name "unconnected-(SD1-DAT1{slash}NC-Pad8)") (class "Default")
      (node (ref "SD1") (pin "8") (pinfunction "DAT1/NC_8") (pintype "passive"))
    )
    (net (code "107") (name "unconnected-(SD1-DAT2{slash}NC-Pad1)") (class "Default")
      (node (ref "SD1") (pin "1") (pinfunction "DAT2/NC_1") (pintype "passive"))
    )
  )
)
